# SD_Card.net
KiCad netlist of a schematic drawn in Altium Designer
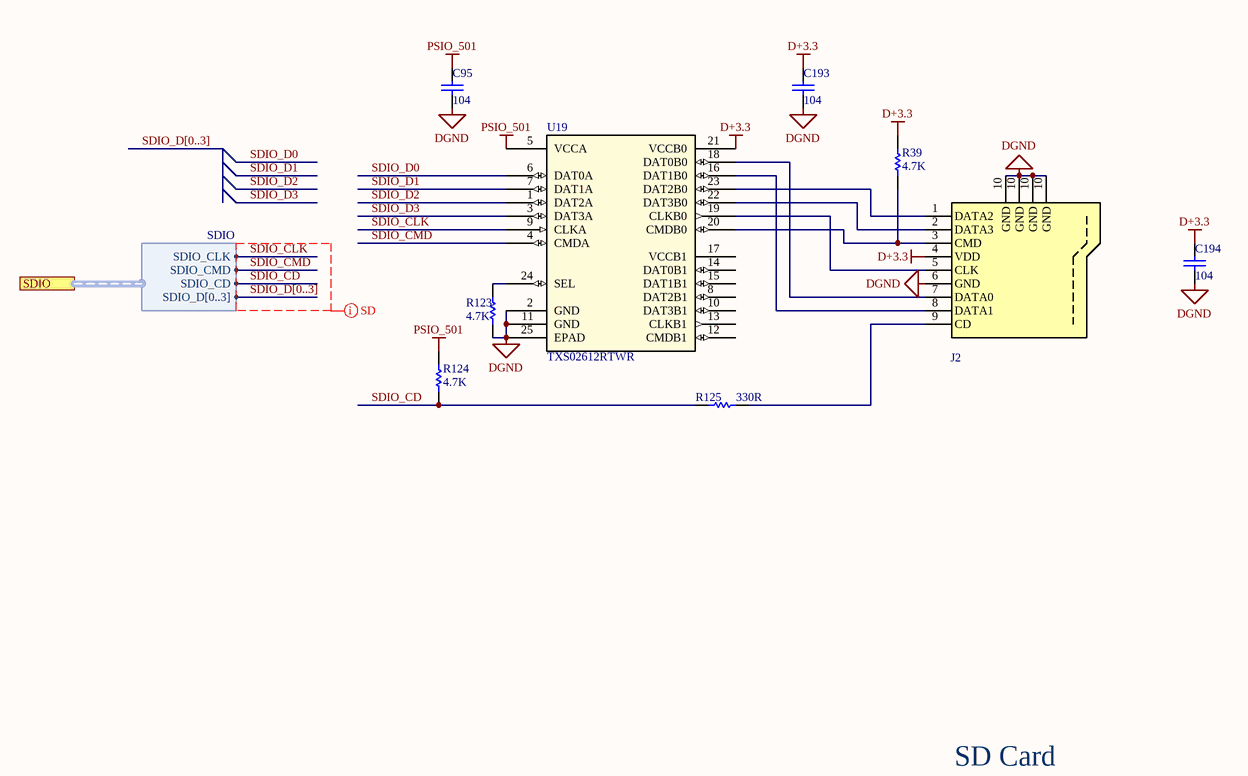
[diagram p0: SD_Card.SchDoc]

(export (version "E")
  (design (tool "Eeschema 10.0.6"))
  (components
    (comp (ref "C95")
      (value "104")
      (footprint "C 0402_LL")
      (description "Capacitor")
      (fields (field (name "PUBLISHER") "Altium Limited"))
      (libsource (lib "Miscellaneous Devices") (part "Cap"))
    )
    (comp (ref "C193")
      (value "104")
      (footprint "C 0402_LL")
      (description "Capacitor")
      (fields (field (name "PUBLISHER") "Altium Limited"))
      (libsource (lib "Miscellaneous Devices") (part "Cap"))
    )
    (comp (ref "C194")
      (value "104")
      (footprint "C 0402_LL")
      (description "Capacitor")
      (fields (field (name "PUBLISHER") "Altium Limited"))
      (libsource (lib "Miscellaneous Devices") (part "Cap"))
    )
    (comp (ref "J2")
      (value "SD_Card")
      (footprint "Micro SD")
      (libsource (lib "ZYNQ7010_add") (part "SD_Card"))
    )
    (comp (ref "R39")
      (value "4.7K")
      (footprint "R 0603_L")
      (description "Resistor")
      (fields (field (name "PUBLISHER") "Altium Limited"))
      (libsource (lib "Miscellaneous Devices") (part "Res1"))
    )
    (comp (ref "R123")
      (value "4.7K")
      (footprint "R 0603_L")
      (description "Resistor")
      (fields (field (name "PUBLISHER") "Altium Limited"))
      (libsource (lib "Miscellaneous Devices") (part "Res1"))
    )
    (comp (ref "R124")
      (value "4.7K")
      (footprint "R 0603_L")
      (description "Resistor")
      (fields (field (name "PUBLISHER") "Altium Limited"))
      (libsource (lib "Miscellaneous Devices") (part "Res1"))
    )
    (comp (ref "R125")
      (value "330R")
      (footprint "R 0603_L")
      (description "Resistor")
      (fields (field (name "PUBLISHER") "Altium Limited"))
      (libsource (lib "Miscellaneous Devices") (part "Res1"))
    )
    (comp (ref "U19")
      (value "TXS02612RTWR")
      (footprint "RTW24_2P45X2P45")
      (description "No Description Available")
      (fields (field (name "COPYRIGHT") "Copyright (C) 2022 Ultra Librarian. All rights reserved."))
      (libsource (lib "XCZU15_add") (part "TXS02612RTWR"))
    )
  )
  (nets
    (net (code "2") (name "/SDIO_CD") (class "Default")
      (node (ref "R124") (pin "2") (pinfunction "2_2") (pintype "passive"))
      (node (ref "R125") (pin "1") (pinfunction "1_1") (pintype "passive"))
    )
    (net (code "3") (name "/SDIO_CLK") (class "Default")
      (node (ref "U19") (pin "9") (pinfunction "CLKA_9") (pintype "input"))
    )
    (net (code "4") (name "/SDIO_CMD") (class "Default")
      (node (ref "U19") (pin "4") (pinfunction "CMDA_4") (pintype "bidirectional"))
    )
    (net (code "5") (name "/SDIO_D0") (class "Default")
      (node (ref "U19") (pin "6") (pinfunction "DAT0A_6") (pintype "bidirectional"))
    )
    (net (code "6") (name "/SDIO_D1") (class "Default")
      (node (ref "U19") (pin "7") (pinfunction "DAT1A_7") (pintype "bidirectional"))
    )
    (net (code "7") (name "/SDIO_D2") (class "Default")
      (node (ref "U19") (pin "1") (pinfunction "DAT2A_1") (pintype "bidirectional"))
    )
    (net (code "8") (name "/SDIO_D3") (class "Default")
      (node (ref "U19") (pin "3") (pinfunction "DAT3A_3") (pintype "bidirectional"))
    )
    (net (code "12") (name "D+3.3") (class "Default")
      (node (ref "C193") (pin "1") (pinfunction "1_1") (pintype "passive"))
      (node (ref "C194") (pin "1") (pinfunction "1_1") (pintype "passive"))
      (node (ref "J2") (pin "4") (pinfunction "VDD_4") (pintype "passive"))
      (node (ref "R39") (pin "1") (pinfunction "1_1") (pintype "passive"))
      (node (ref "U19") (pin "21") (pinfunction "VCCB0_21") (pintype "power_in"))
    )
    (net (code "13") (name "DGND") (class "Default")
      (node (ref "C193") (pin "2") (pinfunction "2_2") (pintype "passive"))
      (node (ref "C194") (pin "2") (pinfunction "2_2") (pintype "passive"))
      (node (ref "C95") (pin "2") (pinfunction "2_2") (pintype "passive"))
      (node (ref "J2") (pin "10") (pinfunction "GND_10") (pintype "passive"))
      (node (ref "J2") (pin "6") (pinfunction "GND_6") (pintype "passive"))
      (node (ref "R123") (pin "2") (pinfunction "2_2") (pintype "passive"))
      (node (ref "U19") (pin "11") (pinfunction "GND_11") (pintype "power_in"))
      (node (ref "U19") (pin "2") (pinfunction "GND_2") (pintype "power_in"))
      (node (ref "U19") (pin "25") (pinfunction "EPAD_25") (pintype "passive"))
    )
    (net (code "14") (name "Net-(J2-CD)") (class "Default")
      (node (ref "J2") (pin "9") (pinfunction "CD_9") (pintype "passive"))
      (node (ref "R125") (pin "2") (pinfunction "2_2") (pintype "passive"))
    )
    (net (code "15") (name "Net-(J2-CLK)") (class "Default")
      (node (ref "J2") (pin "5") (pinfunction "CLK_5") (pintype "passive"))
      (node (ref "U19") (pin "19") (pinfunction "CLKB0_19") (pintype "output"))
    )
    (net (code "16") (name "Net-(J2-CMD)") (class "Default")
      (node (ref "J2") (pin "3") (pinfunction "CMD_3") (pintype "passive"))
      (node (ref "R39") (pin "2") (pinfunction "2_2") (pintype "passive"))
      (node (ref "U19") (pin "20") (pinfunction "CMDB0_20") (pintype "bidirectional"))
    )
    (net (code "17") (name "Net-(J2-DATA0)") (class "Default")
      (node (ref "J2") (pin "7") (pinfunction "DATA0_7") (pintype "passive"))
      (node (ref "U19") (pin "18") (pinfunction "DAT0B0_18") (pintype "bidirectional"))
    )
    (net (code "18") (name "Net-(J2-DATA1)") (class "Default")
      (node (ref "J2") (pin "8") (pinfunction "DATA1_8") (pintype "passive"))
      (node (ref "U19") (pin "16") (pinfunction "DAT1B0_16") (pintype "bidirectional"))
    )
    (net (code "19") (name "Net-(J2-DATA2)") (class "Default")
      (node (ref "J2") (pin "1") (pinfunction "DATA2_1") (pintype "passive"))
      (node (ref "U19") (pin "23") (pinfunction "DAT2B0_23") (pintype "bidirectional"))
    )
    (net (code "20") (name "Net-(J2-DATA3)") (class "Default")
      (node (ref "J2") (pin "2") (pinfunction "DATA3_2") (pintype "passive"))
      (node (ref "U19") (pin "22") (pinfunction "DAT3B0_22") (pintype "bidirectional"))
    )
    (net (code "21") (name "Net-(U19-SEL)") (class "Default")
      (node (ref "R123") (pin "1") (pinfunction "1_1") (pintype "passive"))
      (node (ref "U19") (pin "24") (pinfunction "SEL_24") (pintype "bidirectional"))
    )
    (net (code "22") (name "PSIO_501") (class "Default")
      (node (ref "C95") (pin "1") (pinfunction "1_1") (pintype "passive"))
      (node (ref "R124") (pin "1") (pinfunction "1_1") (pintype "passive"))
      (node (ref "U19") (pin "5") (pinfunction "VCCA_5") (pintype "power_in"))
    )
    (net (code "23") (name "unconnected-(U19-CLKB1-Pad13)") (class "Default")
      (node (ref "U19") (pin "13") (pinfunction "CLKB1_13") (pintype "output"))
    )
    (net (code "24") (name "unconnected-(U19-CMDB1-Pad12)") (class "Default")
      (node (ref "U19") (pin "12") (pinfunction "CMDB1_12") (pintype "bidirectional"))
    )
    (net (code "25") (name "unconnected-(U19-DAT0B1-Pad14)") (class "Default")
      (node (ref "U19") (pin "14") (pinfunction "DAT0B1_14") (pintype "bidirectional"))
    )
    (net (code "26") (name "unconnected-(U19-DAT1B1-Pad15)") (class "Default")
      (node (ref "U19") (pin "15") (pinfunction "DAT1B1_15") (pintype "bidirectional"))
    )
    (net (code "27") (name "unconnected-(U19-DAT2B1-Pad8)") (class "Default")
      (node (ref "U19") (pin "8") (pinfunction "DAT2B1_8") (pintype "bidirectional"))
    )
    (net (code "28") (name "unconnected-(U19-DAT3B1-Pad10)") (class "Default")
      (node (ref "U19") (pin "10") (pinfunction "DAT3B1_10") (pintype "bidirectional"))
    )
    (net (code "29") (name "unconnected-(U19-VCCB1-Pad17)") (class "Default")
      (node (ref "U19") (pin "17") (pinfunction "VCCB1_17") (pintype "power_in"))
    )
  )
)
